# Mainboard-Easyeda-source.net
KiCad netlist of a schematic drawn in EasyEDA
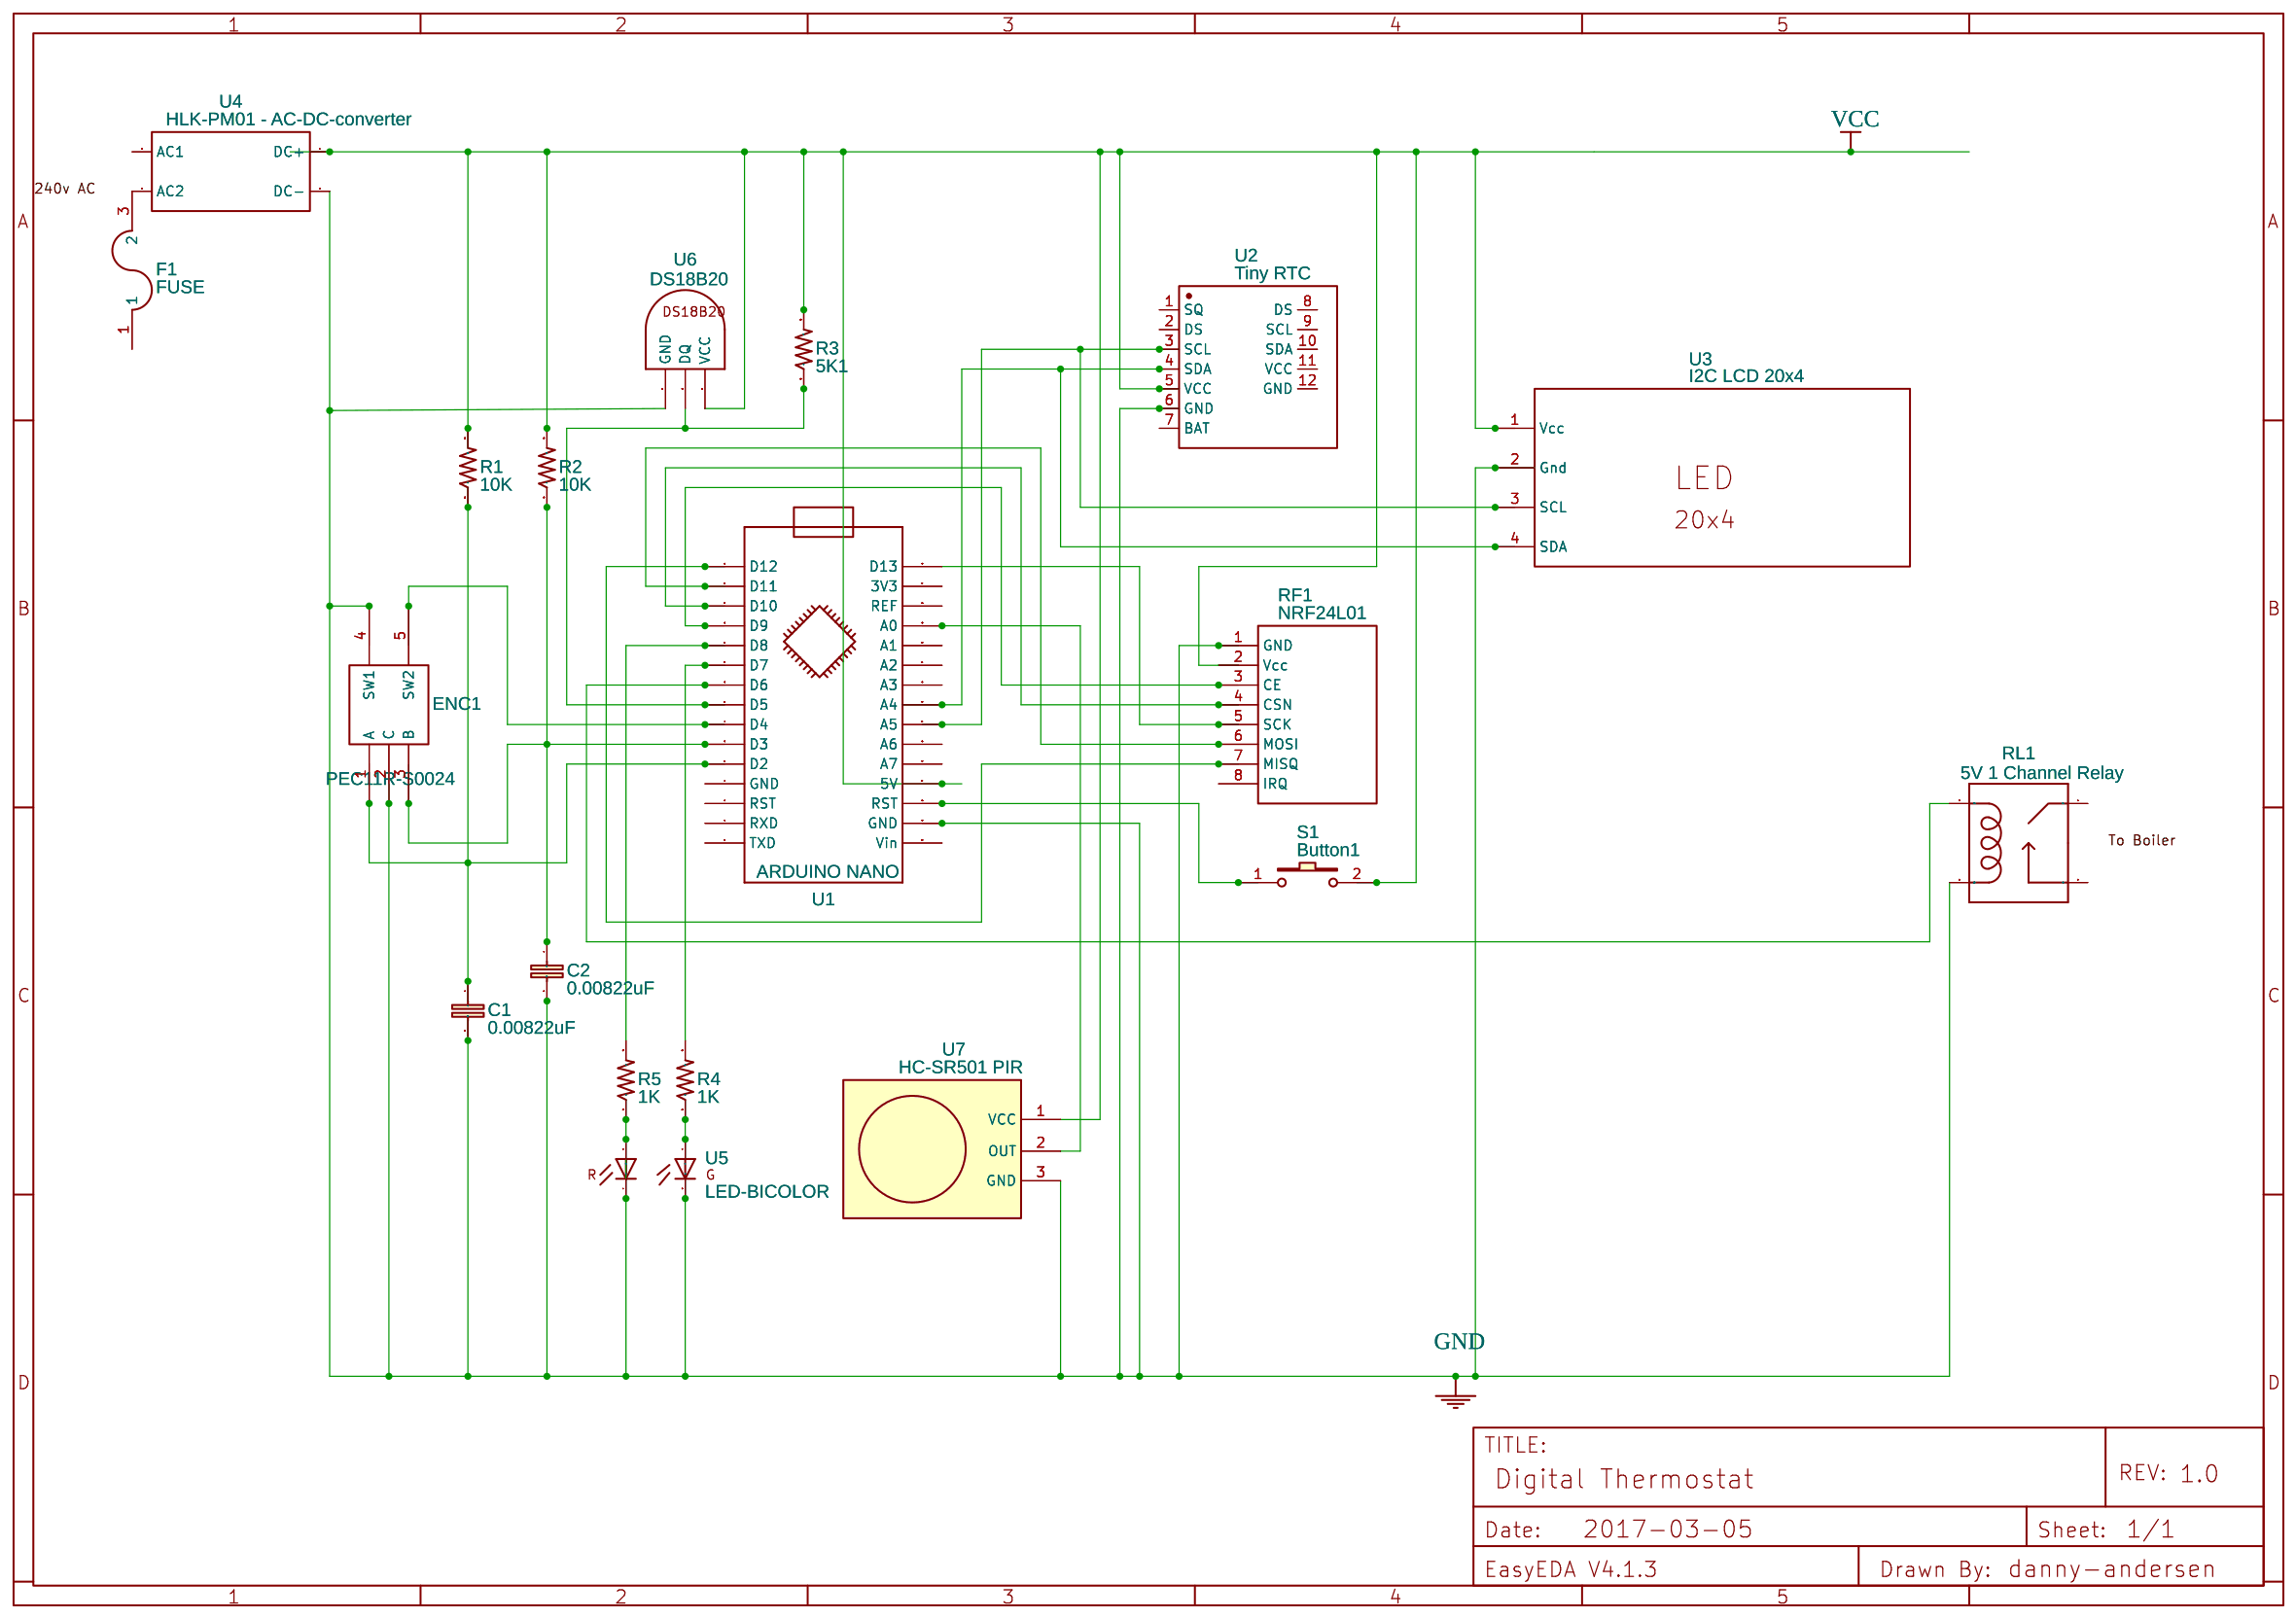
[diagram p0: schematic sheet]

(export (version "E")
  (design (tool "Eeschema 10.0.6"))
  (components
    (comp (ref "C1")
      (value "0.00822uF")
      (fields (field (name "BOM_Manufacturer Part") "?"))
      (libsource (lib "") (part "Unknown_230_510"))
    )
    (comp (ref "C2")
      (value "0.00822uF")
      (fields (field (name "BOM_Manufacturer Part") "?"))
      (libsource (lib "") (part "Unknown_270_490"))
    )
    (comp (ref "ENC1")
      (value "PEC11R-S0024")
      (fields (field (name "BOM_Manufacturer Part") "?"))
      (libsource (lib "") (part "Unknown_190_350"))
    )
    (comp (ref "F1")
      (value "FUSE")
      (fields (field (name "BOM_Manufacturer Part") "?"))
      (libsource (lib "") (part "Unknown_60_130"))
    )
    (comp (ref "R1")
      (value "10K")
      (fields (field (name "BOM_Manufacturer Part") "?"))
      (libsource (lib "") (part "Unknown_230_230"))
    )
    (comp (ref "R2")
      (value "10K")
      (fields (field (name "BOM_Manufacturer Part") "?"))
      (libsource (lib "") (part "Unknown_270_230"))
    )
    (comp (ref "R3")
      (value "5K1")
      (fields (field (name "BOM_Manufacturer Part") "?"))
      (libsource (lib "") (part "Unknown_400_170"))
    )
    (comp (ref "R4")
      (value "1K")
      (fields (field (name "BOM_Manufacturer Part") "?"))
      (libsource (lib "") (part "Unknown_340_540"))
    )
    (comp (ref "R5")
      (value "1K")
      (fields (field (name "BOM_Manufacturer Part") "?"))
      (libsource (lib "") (part "Unknown_310_540"))
    )
    (comp (ref "RF1")
      (value "NRF24L01")
      (fields (field (name "BOM_Manufacturer Part") "?"))
      (libsource (lib "") (part "Unknown_660_350"))
    )
    (comp (ref "RL1")
      (value "5V 1 Channel Relay")
      (fields (field (name "BOM_Manufacturer Part") "?"))
      (libsource (lib "") (part "Unknown_1020_420"))
    )
    (comp (ref "S1")
      (value "Button1")
      (fields (field (name "BOM_Manufacturer Part") "?"))
      (libsource (lib "") (part "Unknown_650_440"))
    )
    (comp (ref "U1")
      (value "ARDUINO NANO")
      (fields (field (name "BOM_Manufacturer Part") "?"))
      (libsource (lib "") (part "Unknown_470_260"))
    )
    (comp (ref "U2")
      (value "Tiny RTC")
      (fields (field (name "BOM_Manufacturer Part") "?"))
      (libsource (lib "") (part "Unknown_620_140"))
    )
    (comp (ref "U3")
      (value "I2C LCD 20x4")
      (fields (field (name "BOM_Manufacturer Part") "?"))
      (libsource (lib "") (part "Unknown_770_190"))
    )
    (comp (ref "U4")
      (value "HLK-PM01 - AC-DC-converter")
      (fields (field (name "BOM_Manufacturer Part") "?"))
      (libsource (lib "") (part "Unknown_100_80"))
    )
    (comp (ref "U5")
      (value "LED-BICOLOR")
      (fields (field (name "BOM_Manufacturer Part") "?"))
      (libsource (lib "") (part "Unknown_310_580"))
    )
    (comp (ref "U6")
      (value "DS18B20")
      (fields (field (name "BOM_Manufacturer Part") "?"))
      (libsource (lib "") (part "Unknown_340_180"))
    )
    (comp (ref "U7")
      (value "HC-SR501 PIR")
      (fields (field (name "BOM_Manufacturer Part") "?"))
      (libsource (lib "") (part "Unknown_420_610"))
    )
  )
  (nets
    (net (code "3") (name "GND") (class "Default")
      (node (ref "C1") (pin "2") (pinfunction "2_2") (pintype "unspecified"))
      (node (ref "C2") (pin "2") (pinfunction "2_2") (pintype "unspecified"))
      (node (ref "ENC1") (pin "2") (pinfunction "C_2") (pintype "unspecified"))
      (node (ref "ENC1") (pin "4") (pinfunction "SW1_4") (pintype "unspecified"))
      (node (ref "R5") (pin "P$1") (pinfunction "1_P$1") (pintype "unspecified"))
      (node (ref "RF1") (pin "1") (pinfunction "GND_1") (pintype "unspecified"))
      (node (ref "RL1") (pin "5") (pinfunction "COIL1_5") (pintype "unspecified"))
      (node (ref "U1") (pin "29") (pinfunction "GND_29") (pintype "unspecified"))
      (node (ref "U2") (pin "6") (pinfunction "GND_6") (pintype "unspecified"))
      (node (ref "U3") (pin "2") (pinfunction "Gnd_2") (pintype "unspecified"))
      (node (ref "U4") (pin "3") (pinfunction "DC-_3") (pintype "unspecified"))
      (node (ref "U5") (pin "2") (pinfunction "2_2") (pintype "unspecified"))
      (node (ref "U5") (pin "3") (pinfunction "3_3") (pintype "unspecified"))
      (node (ref "U5") (pin "4") (pinfunction "4_4") (pintype "unspecified"))
      (node (ref "U6") (pin "GND") (pinfunction "GND_GND") (pintype "passive"))
      (node (ref "U7") (pin "3") (pinfunction "GND_3") (pintype "unspecified"))
    )
    (net (code "4") (name "Net-(ENC1-A)") (class "Default")
      (node (ref "C1") (pin "1") (pinfunction "1_1") (pintype "unspecified"))
      (node (ref "ENC1") (pin "1") (pinfunction "A_1") (pintype "output"))
      (node (ref "R1") (pin "P$1") (pinfunction "1_P$1") (pintype "unspecified"))
      (node (ref "U1") (pin "5") (pinfunction "D2_5") (pintype "unspecified"))
    )
    (net (code "5") (name "Net-(ENC1-B)") (class "Default")
      (node (ref "C2") (pin "1") (pinfunction "1_1") (pintype "unspecified"))
      (node (ref "ENC1") (pin "3") (pinfunction "B_3") (pintype "output"))
      (node (ref "R2") (pin "P$1") (pinfunction "1_P$1") (pintype "unspecified"))
      (node (ref "U1") (pin "6") (pinfunction "D3_6") (pintype "unspecified"))
    )
    (net (code "6") (name "Net-(ENC1-SW2)") (class "Default")
      (node (ref "ENC1") (pin "5") (pinfunction "SW2_5") (pintype "unspecified"))
      (node (ref "U1") (pin "7") (pinfunction "D4_7") (pintype "unspecified"))
    )
    (net (code "7") (name "Net-(F1-2)") (class "Default")
      (node (ref "F1") (pin "3") (pinfunction "2_3") (pintype "unspecified"))
      (node (ref "U4") (pin "2") (pinfunction "AC2_2") (pintype "input"))
    )
    (net (code "8") (name "Net-(R3-1)") (class "Default")
      (node (ref "R3") (pin "P$1") (pinfunction "1_P$1") (pintype "unspecified"))
      (node (ref "U1") (pin "8") (pinfunction "D5_8") (pintype "unspecified"))
      (node (ref "U6") (pin "DQ") (pinfunction "DQ_DQ") (pintype "unspecified"))
    )
    (net (code "9") (name "Net-(R4-1)") (class "Default")
      (node (ref "R4") (pin "P$1") (pinfunction "1_P$1") (pintype "unspecified"))
      (node (ref "U5") (pin "1") (pinfunction "1_1") (pintype "unspecified"))
    )
    (net (code "10") (name "Net-(R4-2)") (class "Default")
      (node (ref "R4") (pin "P$2") (pinfunction "2_P$2") (pintype "unspecified"))
      (node (ref "U1") (pin "10") (pinfunction "D7_10") (pintype "unspecified"))
    )
    (net (code "11") (name "Net-(R5-2)") (class "Default")
      (node (ref "R5") (pin "P$2") (pinfunction "2_P$2") (pintype "unspecified"))
      (node (ref "U1") (pin "11") (pinfunction "D8_11") (pintype "unspecified"))
    )
    (net (code "12") (name "Net-(RF1-CE)") (class "Default")
      (node (ref "RF1") (pin "3") (pinfunction "CE_3") (pintype "unspecified"))
      (node (ref "U1") (pin "12") (pinfunction "D9_12") (pintype "unspecified"))
    )
    (net (code "13") (name "Net-(RF1-CSN)") (class "Default")
      (node (ref "RF1") (pin "4") (pinfunction "CSN_4") (pintype "unspecified"))
      (node (ref "U1") (pin "13") (pinfunction "D10_13") (pintype "unspecified"))
    )
    (net (code "14") (name "Net-(RF1-MISQ)") (class "Default")
      (node (ref "RF1") (pin "7") (pinfunction "MISQ_7") (pintype "unspecified"))
      (node (ref "U1") (pin "15") (pinfunction "D12_15") (pintype "unspecified"))
    )
    (net (code "15") (name "Net-(RF1-MOSI)") (class "Default")
      (node (ref "RF1") (pin "6") (pinfunction "MOSI_6") (pintype "unspecified"))
      (node (ref "U1") (pin "14") (pinfunction "D11_14") (pintype "unspecified"))
    )
    (net (code "16") (name "Net-(RF1-SCK)") (class "Default")
      (node (ref "RF1") (pin "5") (pinfunction "SCK_5") (pintype "unspecified"))
      (node (ref "U1") (pin "16") (pinfunction "D13_16") (pintype "unspecified"))
    )
    (net (code "17") (name "Net-(RL1-COIL2)") (class "Default")
      (node (ref "RL1") (pin "2") (pinfunction "COIL2_2") (pintype "unspecified"))
      (node (ref "U1") (pin "9") (pinfunction "D6_9") (pintype "unspecified"))
    )
    (net (code "18") (name "Net-(S1-Pad1)") (class "Default")
      (node (ref "S1") (pin "1") (pintype "unspecified"))
      (node (ref "U1") (pin "28") (pinfunction "RST_28") (pintype "unspecified"))
    )
    (net (code "19") (name "Net-(U1-A0)") (class "Default")
      (node (ref "U1") (pin "19") (pinfunction "A0_19") (pintype "unspecified"))
      (node (ref "U7") (pin "2") (pinfunction "OUT_2") (pintype "unspecified"))
    )
    (net (code "20") (name "Net-(U1-A4)") (class "Default")
      (node (ref "U1") (pin "23") (pinfunction "A4_23") (pintype "unspecified"))
      (node (ref "U2") (pin "4") (pinfunction "SDA_4") (pintype "unspecified"))
      (node (ref "U3") (pin "4") (pinfunction "SDA_4") (pintype "unspecified"))
    )
    (net (code "21") (name "Net-(U1-A5)") (class "Default")
      (node (ref "U1") (pin "24") (pinfunction "A5_24") (pintype "unspecified"))
      (node (ref "U2") (pin "3") (pinfunction "SCL_3") (pintype "unspecified"))
      (node (ref "U3") (pin "3") (pinfunction "SCL_3") (pintype "unspecified"))
    )
    (net (code "22") (name "VCC") (class "Default")
      (node (ref "R1") (pin "P$2") (pinfunction "2_P$2") (pintype "unspecified"))
      (node (ref "R2") (pin "P$2") (pinfunction "2_P$2") (pintype "unspecified"))
      (node (ref "R3") (pin "P$2") (pinfunction "2_P$2") (pintype "unspecified"))
      (node (ref "RF1") (pin "2") (pinfunction "Vcc_2") (pintype "unspecified"))
      (node (ref "S1") (pin "2") (pintype "unspecified"))
      (node (ref "U1") (pin "27") (pinfunction "5V_27") (pintype "unspecified"))
      (node (ref "U2") (pin "5") (pinfunction "VCC_5") (pintype "unspecified"))
      (node (ref "U3") (pin "1") (pinfunction "Vcc_1") (pintype "unspecified"))
      (node (ref "U4") (pin "4") (pinfunction "DC+_4") (pintype "unspecified"))
      (node (ref "U6") (pin "VCC") (pinfunction "VCC_VCC") (pintype "passive"))
      (node (ref "U7") (pin "1") (pinfunction "VCC_1") (pintype "unspecified"))
    )
    (net (code "23") (name "unconnected-(F1-Pad1)") (class "Default")
      (node (ref "F1") (pin "1") (pinfunction "1_1") (pintype "unspecified"))
    )
    (net (code "24") (name "unconnected-(RF1-IRQ-Pad8)") (class "Default")
      (node (ref "RF1") (pin "8") (pinfunction "IRQ_8") (pintype "unspecified"))
    )
    (net (code "25") (name "unconnected-(RL1-MAIN-Pad1)") (class "Default")
      (node (ref "RL1") (pin "1") (pinfunction "MAIN_1") (pintype "unspecified"))
    )
    (net (code "26") (name "unconnected-(RL1-NO-Pad3)") (class "Default")
      (node (ref "RL1") (pin "3") (pinfunction "NO_3") (pintype "unspecified"))
    )
    (net (code "27") (name "unconnected-(U1-3V3-Pad17)") (class "Default")
      (node (ref "U1") (pin "17") (pinfunction "3V3_17") (pintype "unspecified"))
    )
    (net (code "28") (name "unconnected-(U1-A1-Pad20)") (class "Default")
      (node (ref "U1") (pin "20") (pinfunction "A1_20") (pintype "unspecified"))
    )
    (net (code "29") (name "unconnected-(U1-A2-Pad21)") (class "Default")
      (node (ref "U1") (pin "21") (pinfunction "A2_21") (pintype "unspecified"))
    )
    (net (code "30") (name "unconnected-(U1-A3-Pad22)") (class "Default")
      (node (ref "U1") (pin "22") (pinfunction "A3_22") (pintype "unspecified"))
    )
    (net (code "31") (name "unconnected-(U1-A6-Pad25)") (class "Default")
      (node (ref "U1") (pin "25") (pinfunction "A6_25") (pintype "unspecified"))
    )
    (net (code "32") (name "unconnected-(U1-A7-Pad26)") (class "Default")
      (node (ref "U1") (pin "26") (pinfunction "A7_26") (pintype "unspecified"))
    )
    (net (code "33") (name "unconnected-(U1-GND-Pad4)") (class "Default")
      (node (ref "U1") (pin "4") (pinfunction "GND_4") (pintype "unspecified"))
    )
    (net (code "34") (name "unconnected-(U1-REF-Pad18)") (class "Default")
      (node (ref "U1") (pin "18") (pinfunction "REF_18") (pintype "unspecified"))
    )
    (net (code "35") (name "unconnected-(U1-RST-Pad3)") (class "Default")
      (node (ref "U1") (pin "3") (pinfunction "RST_3") (pintype "unspecified"))
    )
    (net (code "36") (name "unconnected-(U1-RXD-Pad2)") (class "Default")
      (node (ref "U1") (pin "2") (pinfunction "RXD_2") (pintype "unspecified"))
    )
    (net (code "37") (name "unconnected-(U1-TXD-Pad1)") (class "Default")
      (node (ref "U1") (pin "1") (pinfunction "TXD_1") (pintype "unspecified"))
    )
    (net (code "38") (name "unconnected-(U1-Vin-Pad30)") (class "Default")
      (node (ref "U1") (pin "30") (pinfunction "Vin_30") (pintype "unspecified"))
    )
    (net (code "39") (name "unconnected-(U2-BAT-Pad7)") (class "Default")
      (node (ref "U2") (pin "7") (pinfunction "BAT_7") (pintype "unspecified"))
    )
    (net (code "40") (name "unconnected-(U2-DS-Pad2)") (class "Default")
      (node (ref "U2") (pin "2") (pinfunction "DS_2") (pintype "unspecified"))
    )
    (net (code "41") (name "unconnected-(U2-DS-Pad8)") (class "Default")
      (node (ref "U2") (pin "8") (pinfunction "DS_8") (pintype "unspecified"))
    )
    (net (code "42") (name "unconnected-(U2-GND-Pad12)") (class "Default")
      (node (ref "U2") (pin "12") (pinfunction "GND_12") (pintype "unspecified"))
    )
    (net (code "43") (name "unconnected-(U2-SCL-Pad9)") (class "Default")
      (node (ref "U2") (pin "9") (pinfunction "SCL_9") (pintype "unspecified"))
    )
    (net (code "44") (name "unconnected-(U2-SDA-Pad10)") (class "Default")
      (node (ref "U2") (pin "10") (pinfunction "SDA_10") (pintype "unspecified"))
    )
    (net (code "45") (name "unconnected-(U2-SQ-Pad1)") (class "Default")
      (node (ref "U2") (pin "1") (pinfunction "SQ_1") (pintype "unspecified"))
    )
    (net (code "46") (name "unconnected-(U2-VCC-Pad11)") (class "Default")
      (node (ref "U2") (pin "11") (pinfunction "VCC_11") (pintype "unspecified"))
    )
    (net (code "47") (name "unconnected-(U4-AC1-Pad1)") (class "Default")
      (node (ref "U4") (pin "1") (pinfunction "AC1_1") (pintype "input"))
    )
  )
)
